# msp430g2553.net
KiCad netlist of a schematic drawn in Altium Designer
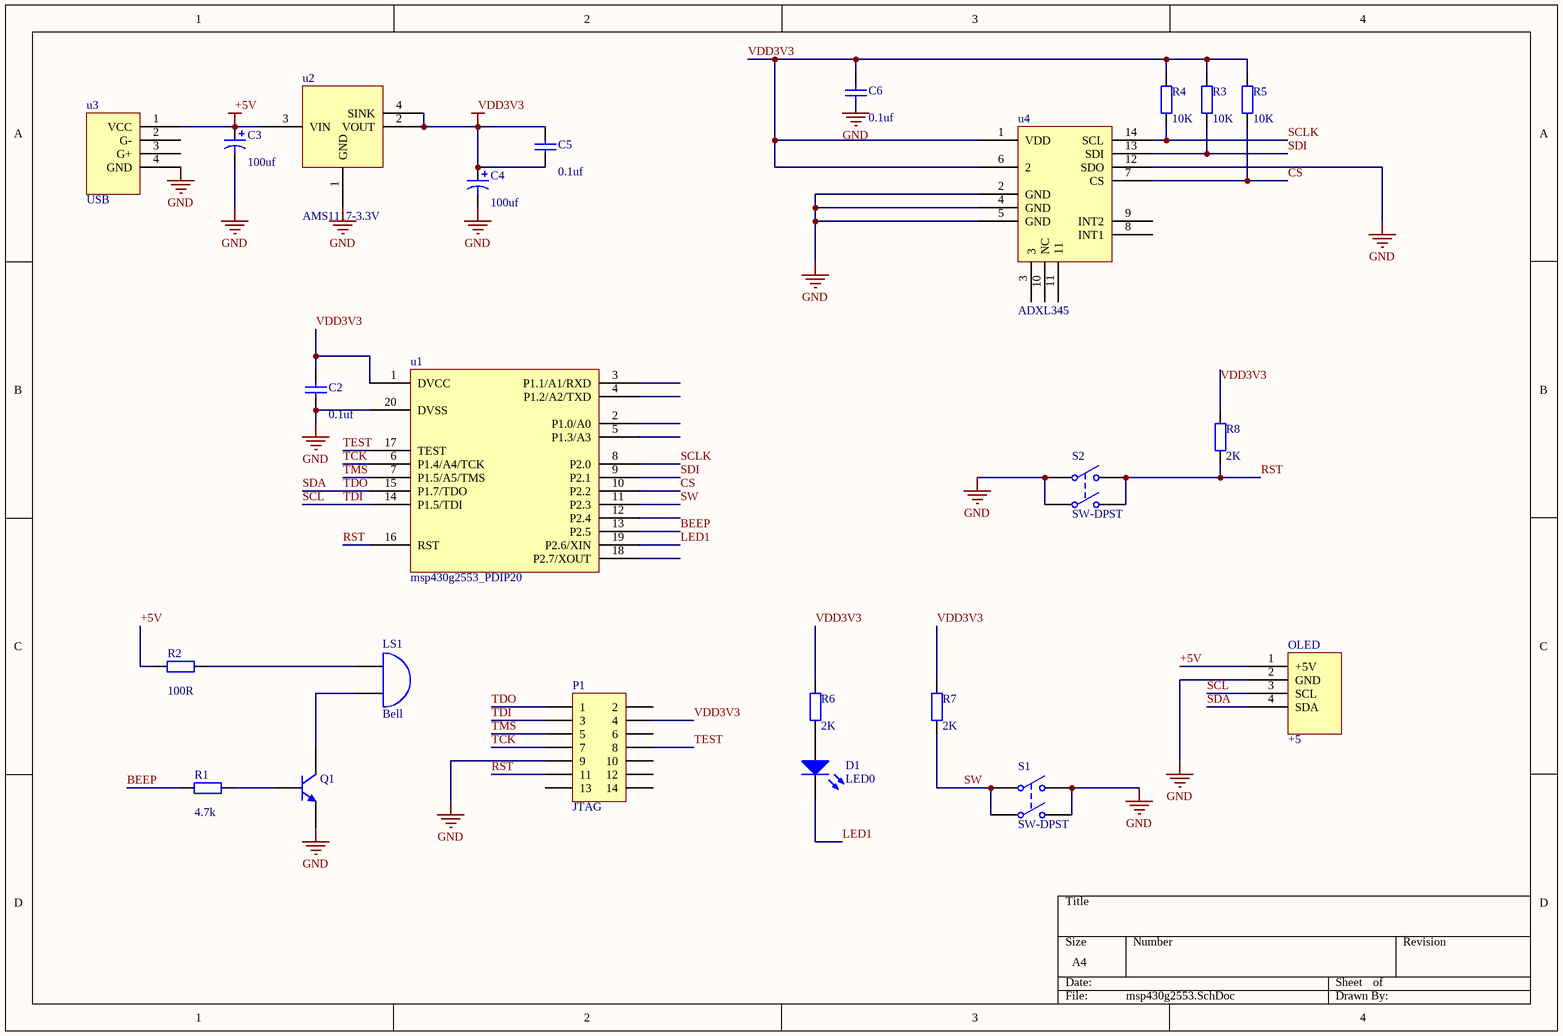
[diagram p0: msp430g2553.SchDoc]

(export (version "E")
  (design (tool "Eeschema 10.0.6"))
  (components
    (comp (ref "C2")
      (value "0.1uf")
      (footprint "6-0805_N")
      (description "Capacitor")
      (fields (field (name "Comment") "Cap") (field (name "PUBLISHER") "Altium Limited"))
      (libsource (lib "msp430g2553") (part "Cap"))
    )
    (comp (ref "C3")
      (value "100uf")
      (footprint "Cap2_polar")
      (description "Polarized Capacitor (Axial)")
      (fields (field (name "Comment") "Cap Pol2") (field (name "PUBLISHER") "Altium Limited"))
      (libsource (lib "msp430g2553") (part "Cap Pol2"))
    )
    (comp (ref "C4")
      (value "100uf")
      (footprint "Cap2_polar")
      (description "Polarized Capacitor (Axial)")
      (fields (field (name "Comment") "Cap Pol2") (field (name "PUBLISHER") "Altium Limited"))
      (libsource (lib "msp430g2553") (part "Cap Pol2"))
    )
    (comp (ref "C5")
      (value "0.1uf")
      (footprint "6-0805_N")
      (description "Capacitor")
      (fields (field (name "Comment") "Cap") (field (name "PUBLISHER") "Altium Limited"))
      (libsource (lib "msp430g2553") (part "Cap"))
    )
    (comp (ref "C6")
      (value "0.1uf")
      (footprint "6-0805_N")
      (description "Capacitor")
      (fields (field (name "Comment") "Cap") (field (name "PUBLISHER") "Altium Limited"))
      (libsource (lib "msp430g2553") (part "Cap"))
    )
    (comp (ref "D1")
      (value "LED0")
      (footprint "6-0805_N - duplicate")
      (description "Typical INFRARED GaAs LED")
      (fields (field (name "PUBLISHER") "Altium Limited"))
      (libsource (lib "msp430g2553") (part "LED0"))
    )
    (comp (ref "LS1")
      (value "Bell")
      (footprint "bell")
      (description "Electrical Bell")
      (fields (field (name "PUBLISHER") "Altium Limited"))
      (libsource (lib "msp430g2553") (part "Bell"))
    )
    (comp (ref "OLED") (value "+5") (footprint "OLED") (libsource (lib "msp430g2553") (part "OLED")))
    (comp (ref "P1")
      (value "JTAG")
      (footprint "HDR2X7")
      (description "Header, 7-Pin, Dual row")
      (fields (field (name "PUBLISHER") "Altium Limited"))
      (libsource (lib "msp430g2553") (part "JTAG"))
    )
    (comp (ref "Q1")
      (value "NPN")
      (footprint "SOT23_N")
      (description "NPN Bipolar Transistor")
      (fields (field (name "PUBLISHER") "Altium Limited"))
      (libsource (lib "msp430g2553") (part "NPN"))
    )
    (comp (ref "R1")
      (value "4.7k")
      (footprint "6-0805_N")
      (description "Resistor")
      (fields (field (name "Comment") "Res2") (field (name "PUBLISHER") "Altium Limited"))
      (libsource (lib "") (part "Res2_1"))
    )
    (comp (ref "R2")
      (value "100R")
      (footprint "6-0805_N")
      (description "Resistor")
      (fields (field (name "Comment") "Res2") (field (name "PUBLISHER") "Altium Limited"))
      (libsource (lib "") (part "Res2_1"))
    )
    (comp (ref "R3")
      (value "10K")
      (footprint "6-0805_N")
      (description "Resistor")
      (fields (field (name "Comment") "Res2") (field (name "PUBLISHER") "Altium Limited"))
      (libsource (lib "msp430g2553") (part "Res2"))
    )
    (comp (ref "R4")
      (value "10K")
      (footprint "6-0805_N")
      (description "Resistor")
      (fields (field (name "Comment") "Res2") (field (name "PUBLISHER") "Altium Limited"))
      (libsource (lib "msp430g2553") (part "Res2"))
    )
    (comp (ref "R5")
      (value "10K")
      (footprint "6-0805_N")
      (description "Resistor")
      (fields (field (name "Comment") "Res2") (field (name "PUBLISHER") "Altium Limited"))
      (libsource (lib "msp430g2553") (part "Res2"))
    )
    (comp (ref "R6")
      (value "2K")
      (footprint "6-0805_N")
      (description "Resistor")
      (fields (field (name "Comment") "Res2") (field (name "PUBLISHER") "Altium Limited"))
      (libsource (lib "msp430g2553") (part "Res2"))
    )
    (comp (ref "R7")
      (value "2K")
      (footprint "6-0805_N")
      (description "Resistor")
      (fields (field (name "Comment") "Res2") (field (name "PUBLISHER") "Altium Limited"))
      (libsource (lib "msp430g2553") (part "Res2"))
    )
    (comp (ref "R8")
      (value "2K")
      (footprint "6-0805_N")
      (description "Resistor")
      (fields (field (name "Comment") "Res2") (field (name "PUBLISHER") "Altium Limited"))
      (libsource (lib "msp430g2553") (part "Res2"))
    )
    (comp (ref "S1")
      (value "SW-DPST")
      (footprint "DPST-4")
      (description "Double-Pole, Single-Throw Switch")
      (fields (field (name "PUBLISHER") "Altium Limited"))
      (libsource (lib "msp430g2553") (part "SW-DPST"))
    )
    (comp (ref "S2")
      (value "SW-DPST")
      (footprint "DPST-4")
      (description "Double-Pole, Single-Throw Switch")
      (fields (field (name "PUBLISHER") "Altium Limited"))
      (libsource (lib "msp430g2553") (part "SW-DPST"))
    )
    (comp (ref "u1")
      (value "msp430g2553_PDIP20")
      (footprint "DIP20")
      (libsource (lib "msp430g2553") (part "msp430g2553_PDIP20"))
    )
    (comp (ref "u2")
      (value "AMS1117-3.3V")
      (footprint "SOT223_N")
      (libsource (lib "msp430g2553") (part "AMS1117-3.3V"))
    )
    (comp (ref "u3") (value "USB") (footprint "USB2.5-2H4") (libsource (lib "msp430g2553") (part "USB")))
    (comp (ref "u4") (value "ADXL345") (footprint "ADXL345") (libsource (lib "msp430g2553") (part "ADXL345")))
  )
  (nets
    (net (code "1") (name "+5") (class "Default")
      (node (ref "C3") (pin "2") (pinfunction "2_2") (pintype "passive"))
      (node (ref "u2") (pin "3") (pinfunction "VIN_3") (pintype "passive"))
      (node (ref "u3") (pin "1") (pinfunction "VCC_1") (pintype "passive"))
    )
    (net (code "2") (name "/+5V") (class "Default")
      (node (ref "OLED") (pin "1") (pinfunction "+5V_1") (pintype "passive"))
      (node (ref "R2") (pin "1") (pinfunction "1_1") (pintype "passive"))
    )
    (net (code "3") (name "/BEEP") (class "Default")
      (node (ref "R1") (pin "1") (pinfunction "1_1") (pintype "passive"))
      (node (ref "u1") (pin "13") (pinfunction "P2.5_13") (pintype "passive"))
    )
    (net (code "4") (name "/CS") (class "Default")
      (node (ref "R5") (pin "1") (pinfunction "1_1") (pintype "passive"))
      (node (ref "u1") (pin "10") (pinfunction "P2.2_10") (pintype "passive"))
      (node (ref "u4") (pin "7") (pinfunction "CS_7") (pintype "passive"))
    )
    (net (code "5") (name "/LED1") (class "Default")
      (node (ref "D1") (pin "2") (pinfunction "K_2") (pintype "passive"))
      (node (ref "u1") (pin "19") (pinfunction "P2.6/XIN_19") (pintype "passive"))
    )
    (net (code "6") (name "/RST") (class "Default")
      (node (ref "P1") (pin "11") (pinfunction "11_11") (pintype "passive"))
      (node (ref "R8") (pin "1") (pinfunction "1_1") (pintype "passive"))
      (node (ref "S2") (pin "3") (pinfunction "NO1_3") (pintype "passive"))
      (node (ref "S2") (pin "4") (pinfunction "NO2_4") (pintype "passive"))
      (node (ref "u1") (pin "16") (pinfunction "RST_16") (pintype "passive"))
    )
    (net (code "7") (name "/SCL") (class "Default")
      (node (ref "OLED") (pin "3") (pinfunction "SCL_3") (pintype "passive"))
      (node (ref "P1") (pin "3") (pinfunction "3_3") (pintype "passive"))
      (node (ref "u1") (pin "14") (pinfunction "P1.5/TDI_14") (pintype "passive"))
    )
    (net (code "8") (name "/SCLK") (class "Default")
      (node (ref "R4") (pin "1") (pinfunction "1_1") (pintype "passive"))
      (node (ref "u1") (pin "8") (pinfunction "P2.0_8") (pintype "passive"))
      (node (ref "u4") (pin "14") (pinfunction "SCL_14") (pintype "passive"))
    )
    (net (code "9") (name "/SDA") (class "Default")
      (node (ref "OLED") (pin "4") (pinfunction "SDA_4") (pintype "passive"))
      (node (ref "P1") (pin "1") (pinfunction "1_1") (pintype "passive"))
      (node (ref "u1") (pin "15") (pinfunction "P1.7/TDO_15") (pintype "passive"))
    )
    (net (code "10") (name "/SDI") (class "Default")
      (node (ref "R3") (pin "1") (pinfunction "1_1") (pintype "passive"))
      (node (ref "u1") (pin "9") (pinfunction "P2.1_9") (pintype "passive"))
      (node (ref "u4") (pin "13") (pinfunction "SDI_13") (pintype "passive"))
    )
    (net (code "11") (name "/SW") (class "Default")
      (node (ref "R7") (pin "1") (pinfunction "1_1") (pintype "passive"))
      (node (ref "S1") (pin "1") (pinfunction "COMMON1_1") (pintype "passive"))
      (node (ref "S1") (pin "2") (pinfunction "COMMON2_2") (pintype "passive"))
      (node (ref "u1") (pin "11") (pinfunction "P2.3_11") (pintype "passive"))
    )
    (net (code "12") (name "/TCK") (class "Default")
      (node (ref "P1") (pin "7") (pinfunction "7_7") (pintype "passive"))
      (node (ref "u1") (pin "6") (pinfunction "P1.4/A4/TCK_6") (pintype "passive"))
    )
    (net (code "13") (name "/TEST") (class "Default")
      (node (ref "P1") (pin "8") (pinfunction "8_8") (pintype "passive"))
      (node (ref "u1") (pin "17") (pinfunction "TEST_17") (pintype "passive"))
    )
    (net (code "14") (name "/TMS") (class "Default")
      (node (ref "P1") (pin "5") (pinfunction "5_5") (pintype "passive"))
      (node (ref "u1") (pin "7") (pinfunction "P1.5/A5/TMS_7") (pintype "passive"))
    )
    (net (code "15") (name "/VDD3V3") (class "Default")
      (node (ref "C2") (pin "2") (pinfunction "2_2") (pintype "passive"))
      (node (ref "C6") (pin "2") (pinfunction "2_2") (pintype "passive"))
      (node (ref "P1") (pin "4") (pinfunction "4_4") (pintype "passive"))
      (node (ref "R3") (pin "2") (pinfunction "2_2") (pintype "passive"))
      (node (ref "R4") (pin "2") (pinfunction "2_2") (pintype "passive"))
      (node (ref "R5") (pin "2") (pinfunction "2_2") (pintype "passive"))
      (node (ref "R6") (pin "2") (pinfunction "2_2") (pintype "passive"))
      (node (ref "R7") (pin "2") (pinfunction "2_2") (pintype "passive"))
      (node (ref "R8") (pin "2") (pinfunction "2_2") (pintype "passive"))
      (node (ref "u1") (pin "1") (pinfunction "DVCC_1") (pintype "passive"))
      (node (ref "u4") (pin "1") (pinfunction "VDD_1") (pintype "passive"))
      (node (ref "u4") (pin "6") (pinfunction "2_6") (pintype "passive"))
    )
    (net (code "16") (name "3.3") (class "Default")
      (node (ref "C4") (pin "2") (pinfunction "2_2") (pintype "passive"))
      (node (ref "C5") (pin "1") (pinfunction "1_1") (pintype "passive"))
      (node (ref "C5") (pin "2") (pinfunction "2_2") (pintype "passive"))
      (node (ref "u2") (pin "2") (pinfunction "VOUT_2") (pintype "passive"))
      (node (ref "u2") (pin "4") (pinfunction "SINK_4") (pintype "passive"))
    )
    (net (code "17") (name "GND") (class "Default")
      (node (ref "C2") (pin "1") (pinfunction "1_1") (pintype "passive"))
      (node (ref "C3") (pin "1") (pinfunction "1_1") (pintype "passive"))
      (node (ref "C4") (pin "1") (pinfunction "1_1") (pintype "passive"))
      (node (ref "C6") (pin "1") (pinfunction "1_1") (pintype "passive"))
      (node (ref "OLED") (pin "2") (pinfunction "GND_2") (pintype "passive"))
      (node (ref "P1") (pin "9") (pinfunction "9_9") (pintype "passive"))
      (node (ref "Q1") (pin "3") (pinfunction "E_3") (pintype "passive"))
      (node (ref "S1") (pin "3") (pinfunction "NO1_3") (pintype "passive"))
      (node (ref "S1") (pin "4") (pinfunction "NO2_4") (pintype "passive"))
      (node (ref "S2") (pin "1") (pinfunction "COMMON1_1") (pintype "passive"))
      (node (ref "S2") (pin "2") (pinfunction "COMMON2_2") (pintype "passive"))
      (node (ref "u1") (pin "20") (pinfunction "DVSS_20") (pintype "passive"))
      (node (ref "u2") (pin "1") (pinfunction "GND_1") (pintype "passive"))
      (node (ref "u3") (pin "4") (pinfunction "GND_4") (pintype "passive"))
      (node (ref "u4") (pin "12") (pinfunction "SDO_12") (pintype "passive"))
      (node (ref "u4") (pin "2") (pinfunction "GND_2") (pintype "passive"))
      (node (ref "u4") (pin "4") (pinfunction "GND_4") (pintype "passive"))
      (node (ref "u4") (pin "5") (pinfunction "GND_5") (pintype "passive"))
    )
    (net (code "18") (name "Net-(D1-A)") (class "Default")
      (node (ref "D1") (pin "1") (pinfunction "A_1") (pintype "passive"))
      (node (ref "R6") (pin "1") (pinfunction "1_1") (pintype "passive"))
    )
    (net (code "19") (name "Net-(LS1-A)") (class "Default")
      (node (ref "LS1") (pin "1") (pinfunction "A_1") (pintype "passive"))
      (node (ref "R2") (pin "2") (pinfunction "2_2") (pintype "passive"))
    )
    (net (code "20") (name "Net-(LS1-B)") (class "Default")
      (node (ref "LS1") (pin "2") (pinfunction "B_2") (pintype "passive"))
      (node (ref "Q1") (pin "1") (pinfunction "C_1") (pintype "passive"))
    )
    (net (code "21") (name "Net-(Q1-B)") (class "Default")
      (node (ref "Q1") (pin "2") (pinfunction "B_2") (pintype "passive"))
      (node (ref "R1") (pin "2") (pinfunction "2_2") (pintype "passive"))
    )
    (net (code "22") (name "unconnected-(P1-Pad2)") (class "Default")
      (node (ref "P1") (pin "2") (pinfunction "2_2") (pintype "passive"))
    )
    (net (code "23") (name "unconnected-(P1-Pad6)") (class "Default")
      (node (ref "P1") (pin "6") (pinfunction "6_6") (pintype "passive"))
    )
    (net (code "24") (name "unconnected-(P1-Pad10)") (class "Default")
      (node (ref "P1") (pin "10") (pinfunction "10_10") (pintype "passive"))
    )
    (net (code "25") (name "unconnected-(P1-Pad12)") (class "Default")
      (node (ref "P1") (pin "12") (pinfunction "12_12") (pintype "passive"))
    )
    (net (code "26") (name "unconnected-(P1-Pad13)") (class "Default")
      (node (ref "P1") (pin "13") (pinfunction "13_13") (pintype "passive"))
    )
    (net (code "27") (name "unconnected-(P1-Pad14)") (class "Default")
      (node (ref "P1") (pin "14") (pinfunction "14_14") (pintype "passive"))
    )
    (net (code "28") (name "unconnected-(u1-P1.0{slash}A0-Pad2)") (class "Default")
      (node (ref "u1") (pin "2") (pinfunction "P1.0/A0_2") (pintype "passive"))
    )
    (net (code "29") (name "unconnected-(u1-P1.1{slash}A1{slash}RXD-Pad3)") (class "Default")
      (node (ref "u1") (pin "3") (pinfunction "P1.1/A1/RXD_3") (pintype "passive"))
    )
    (net (code "30") (name "unconnected-(u1-P1.2{slash}A2{slash}TXD-Pad4)") (class "Default")
      (node (ref "u1") (pin "4") (pinfunction "P1.2/A2/TXD_4") (pintype "passive"))
    )
    (net (code "31") (name "unconnected-(u1-P1.3{slash}A3-Pad5)") (class "Default")
      (node (ref "u1") (pin "5") (pinfunction "P1.3/A3_5") (pintype "passive"))
    )
    (net (code "32") (name "unconnected-(u1-P2.4-Pad12)") (class "Default")
      (node (ref "u1") (pin "12") (pinfunction "P2.4_12") (pintype "passive"))
    )
    (net (code "33") (name "unconnected-(u1-P2.7{slash}XOUT-Pad18)") (class "Default")
      (node (ref "u1") (pin "18") (pinfunction "P2.7/XOUT_18") (pintype "passive"))
    )
    (net (code "34") (name "unconnected-(u3-G+-Pad3)") (class "Default")
      (node (ref "u3") (pin "3") (pinfunction "G+_3") (pintype "passive"))
    )
    (net (code "35") (name "unconnected-(u3-G--Pad2)") (class "Default")
      (node (ref "u3") (pin "2") (pinfunction "G-_2") (pintype "passive"))
    )
    (net (code "36") (name "unconnected-(u4-INT1-Pad8)") (class "Default")
      (node (ref "u4") (pin "8") (pinfunction "INT1_8") (pintype "passive"))
    )
    (net (code "37") (name "unconnected-(u4-INT2-Pad9)") (class "Default")
      (node (ref "u4") (pin "9") (pinfunction "INT2_9") (pintype "passive"))
    )
    (net (code "38") (name "unconnected-(u4-NC-Pad10)") (class "Default")
      (node (ref "u4") (pin "10") (pinfunction "NC_10") (pintype "passive"))
    )
    (net (code "39") (name "unconnected-(u4-Pad3)") (class "Default")
      (node (ref "u4") (pin "3") (pinfunction "3_3") (pintype "passive"))
    )
    (net (code "40") (name "unconnected-(u4-Pad11)") (class "Default")
      (node (ref "u4") (pin "11") (pinfunction "11_11") (pintype "passive"))
    )
  )
)
